# sensor_v2b.net
KiCad netlist of a schematic drawn in EAGLE
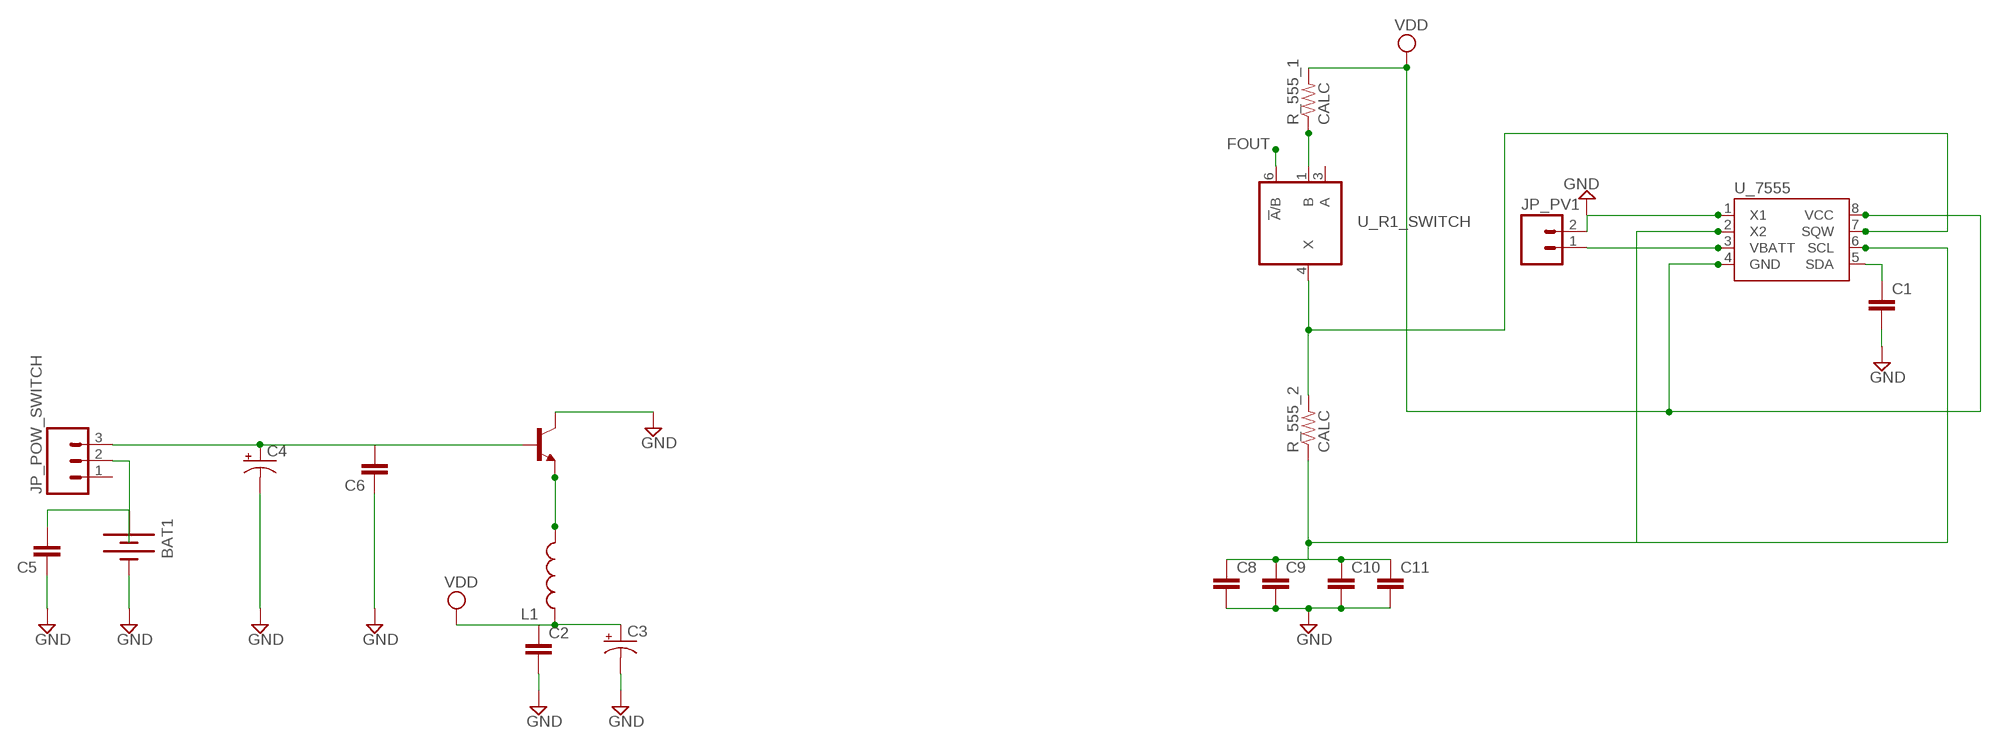
[diagram p0: schematic, sheet 1]

(export (version "E")
  (design (tool "Eeschema 10.0.6"))
  (components
    (comp (ref "BAT1")
      (value "BATTERY20PTH_LAB")
      (footprint "eagle-import:BATTCOM_20MM_PTH")
      (libsource (lib "eagle-import") (part "BATTERY20PTH_LAB"))
    )
    (comp (ref "C1")
      (value "CAP0603-CAP")
      (footprint "eagle-import:0603-CAP")
      (libsource (lib "eagle-import") (part "SparkFun-Capacitors_CAP0603-CAP"))
    )
    (comp (ref "C2")
      (value "CAP0603-CAP")
      (footprint "eagle-import:0603-CAP")
      (libsource (lib "eagle-import") (part "SparkFun-Capacitors_CAP0603-CAP"))
    )
    (comp (ref "C3")
      (value "CAP_POL1206")
      (footprint "eagle-import:EIA3216")
      (libsource (lib "eagle-import") (part "CAP_POL1206"))
    )
    (comp (ref "C4")
      (value "CAP_POL1206")
      (footprint "eagle-import:EIA3216")
      (libsource (lib "eagle-import") (part "CAP_POL1206"))
    )
    (comp (ref "C5")
      (value "CAP0603-CAP")
      (footprint "eagle-import:0603-CAP")
      (libsource (lib "eagle-import") (part "SparkFun-Capacitors_CAP0603-CAP"))
    )
    (comp (ref "C6")
      (value "CAP0603-CAP")
      (footprint "eagle-import:0603-CAP")
      (libsource (lib "eagle-import") (part "SparkFun-Capacitors_CAP0603-CAP"))
    )
    (comp (ref "C8")
      (value "CAP0805")
      (footprint "eagle-import:0805")
      (libsource (lib "eagle-import") (part "CAP0805"))
    )
    (comp (ref "C9")
      (value "CAP0805")
      (footprint "eagle-import:0805")
      (libsource (lib "eagle-import") (part "CAP0805"))
    )
    (comp (ref "C10")
      (value "CAP0805")
      (footprint "eagle-import:0805")
      (libsource (lib "eagle-import") (part "CAP0805"))
    )
    (comp (ref "C11")
      (value "CAP0805")
      (footprint "eagle-import:0805")
      (libsource (lib "eagle-import") (part "CAP0805"))
    )
    (comp (ref "JP_POW_SWITCH")
      (value "M03LOCK")
      (footprint "eagle-import:1X03_LOCK")
      (libsource (lib "eagle-import") (part "M03LOCK"))
    )
    (comp (ref "JP_PV1")
      (value "M02LOCK")
      (footprint "eagle-import:1X02_LOCK")
      (libsource (lib "eagle-import") (part "M02LOCK"))
    )
    (comp (ref "L1")
      (value "INDUCTOR0603")
      (footprint "eagle-import:0603")
      (libsource (lib "eagle-import") (part "INDUCTOR0603"))
    )
    (comp (ref "R_555_1")
      (value "CALC")
      (footprint "eagle-import:0805")
      (libsource (lib "eagle-import") (part "RESISTOR0805-RES"))
    )
    (comp (ref "R_555_2")
      (value "CALC")
      (footprint "eagle-import:0805")
      (libsource (lib "eagle-import") (part "RESISTOR0805-RES"))
    )
    (comp (ref "U_7555")
      (value "DS1307SO8")
      (footprint "eagle-import:SO08")
      (libsource (lib "eagle-import") (part "DS1307SO8"))
    )
    (comp (ref "U_R1_SWITCH")
      (value "741G3157DCKR")
      (footprint "eagle-import:DCK_R-PDSO-G6")
      (libsource (lib "eagle-import") (part "741G3157DCKR"))
    )
    (comp (ref "U_VREF")
      (value "TRANSISTOR_NPNSOT23-3")
      (footprint "eagle-import:SOT23-3")
      (libsource (lib "eagle-import") (part "TRANSISTOR_NPNSOT23-3"))
    )
  )
  (nets
    (net (code "1") (name "/FOUT") (class "Default")
      (node (ref "JP_PV1") (pin "1") (pinfunction "1_1") (pintype "passive"))
      (node (ref "U_7555") (pin "3") (pinfunction "VBATT_3") (pintype "bidirectional"))
      (node (ref "U_R1_SWITCH") (pin "6") (pinfunction "~{A}/B_6") (pintype "input"))
    )
    (net (code "2") (name "/P2") (class "Default")
      (node (ref "C10") (pin "1") (pinfunction "1_1") (pintype "passive"))
      (node (ref "C11") (pin "1") (pinfunction "1_1") (pintype "passive"))
      (node (ref "C8") (pin "1") (pinfunction "1_1") (pintype "passive"))
      (node (ref "C9") (pin "1") (pinfunction "1_1") (pintype "passive"))
      (node (ref "R_555_2") (pin "1") (pinfunction "1_1") (pintype "passive"))
      (node (ref "U_7555") (pin "2") (pinfunction "X2_2") (pintype "bidirectional"))
      (node (ref "U_7555") (pin "6") (pinfunction "SCL_6") (pintype "bidirectional"))
    )
    (net (code "3") (name "GND") (class "Default")
      (node (ref "BAT1") (pin "2") (pinfunction "-_2") (pintype "power_in"))
      (node (ref "C1") (pin "2") (pinfunction "2_2") (pintype "passive"))
      (node (ref "C10") (pin "2") (pinfunction "2_2") (pintype "passive"))
      (node (ref "C11") (pin "2") (pinfunction "2_2") (pintype "passive"))
      (node (ref "C2") (pin "2") (pinfunction "2_2") (pintype "passive"))
      (node (ref "C3") (pin "C") (pinfunction "-_C") (pintype "passive"))
      (node (ref "C4") (pin "C") (pinfunction "-_C") (pintype "passive"))
      (node (ref "C5") (pin "1") (pinfunction "1_1") (pintype "passive"))
      (node (ref "C6") (pin "1") (pinfunction "1_1") (pintype "passive"))
      (node (ref "C8") (pin "2") (pinfunction "2_2") (pintype "passive"))
      (node (ref "C9") (pin "2") (pinfunction "2_2") (pintype "passive"))
      (node (ref "JP_PV1") (pin "2") (pinfunction "2_2") (pintype "passive"))
      (node (ref "U_7555") (pin "1") (pinfunction "X1_1") (pintype "bidirectional"))
      (node (ref "U_VREF") (pin "3") (pinfunction "C_3") (pintype "passive"))
    )
    (net (code "4") (name "Net-(BAT1-+)") (class "Default")
      (node (ref "BAT1") (pin "1") (pinfunction "+_1") (pintype "power_in"))
      (node (ref "C5") (pin "2") (pinfunction "2_2") (pintype "passive"))
      (node (ref "JP_POW_SWITCH") (pin "2") (pinfunction "2_2") (pintype "passive"))
    )
    (net (code "5") (name "Net-(C4-+)") (class "Default")
      (node (ref "C4") (pin "A") (pinfunction "+_A") (pintype "passive"))
      (node (ref "C6") (pin "2") (pinfunction "2_2") (pintype "passive"))
      (node (ref "JP_POW_SWITCH") (pin "3") (pinfunction "3_3") (pintype "passive"))
      (node (ref "U_VREF") (pin "1") (pinfunction "B_1") (pintype "passive"))
    )
    (net (code "6") (name "Net-(U_7555-SDA)") (class "Default")
      (node (ref "C1") (pin "1") (pinfunction "1_1") (pintype "passive"))
      (node (ref "U_7555") (pin "5") (pinfunction "SDA_5") (pintype "bidirectional"))
    )
    (net (code "7") (name "Net-(U_7555-SQW)") (class "Default")
      (node (ref "R_555_2") (pin "2") (pinfunction "2_2") (pintype "passive"))
      (node (ref "U_7555") (pin "7") (pinfunction "SQW_7") (pintype "bidirectional"))
      (node (ref "U_R1_SWITCH") (pin "4") (pinfunction "X_4") (pintype "bidirectional"))
    )
    (net (code "8") (name "Net-(U_R1_SWITCHA-B)") (class "Default")
      (node (ref "R_555_1") (pin "1") (pinfunction "1_1") (pintype "passive"))
      (node (ref "U_R1_SWITCH") (pin "1") (pinfunction "B_1") (pintype "bidirectional"))
    )
    (net (code "9") (name "Net-(U_VREF-E)") (class "Default")
      (node (ref "L1") (pin "2") (pinfunction "2_2") (pintype "passive"))
      (node (ref "U_VREF") (pin "2") (pinfunction "E_2") (pintype "passive"))
    )
    (net (code "10") (name "VDD") (class "Default")
      (node (ref "C2") (pin "1") (pinfunction "1_1") (pintype "passive"))
      (node (ref "C3") (pin "A") (pinfunction "+_A") (pintype "passive"))
      (node (ref "L1") (pin "1") (pinfunction "1_1") (pintype "passive"))
      (node (ref "R_555_1") (pin "2") (pinfunction "2_2") (pintype "passive"))
      (node (ref "U_7555") (pin "4") (pinfunction "GND_4") (pintype "bidirectional"))
      (node (ref "U_7555") (pin "8") (pinfunction "VCC_8") (pintype "bidirectional"))
    )
    (net (code "11") (name "unconnected-(JP_POW_SWITCH-Pad1)") (class "Default")
      (node (ref "JP_POW_SWITCH") (pin "1") (pinfunction "1_1") (pintype "passive"))
    )
    (net (code "12") (name "unconnected-(U_R1_SWITCHA-A-Pad3)") (class "Default")
      (node (ref "U_R1_SWITCH") (pin "3") (pinfunction "A_3") (pintype "bidirectional"))
    )
  )
)
